# SparkFun_Qwiic_6DoF_BMI270.net
KiCad netlist of a schematic drawn in EAGLE
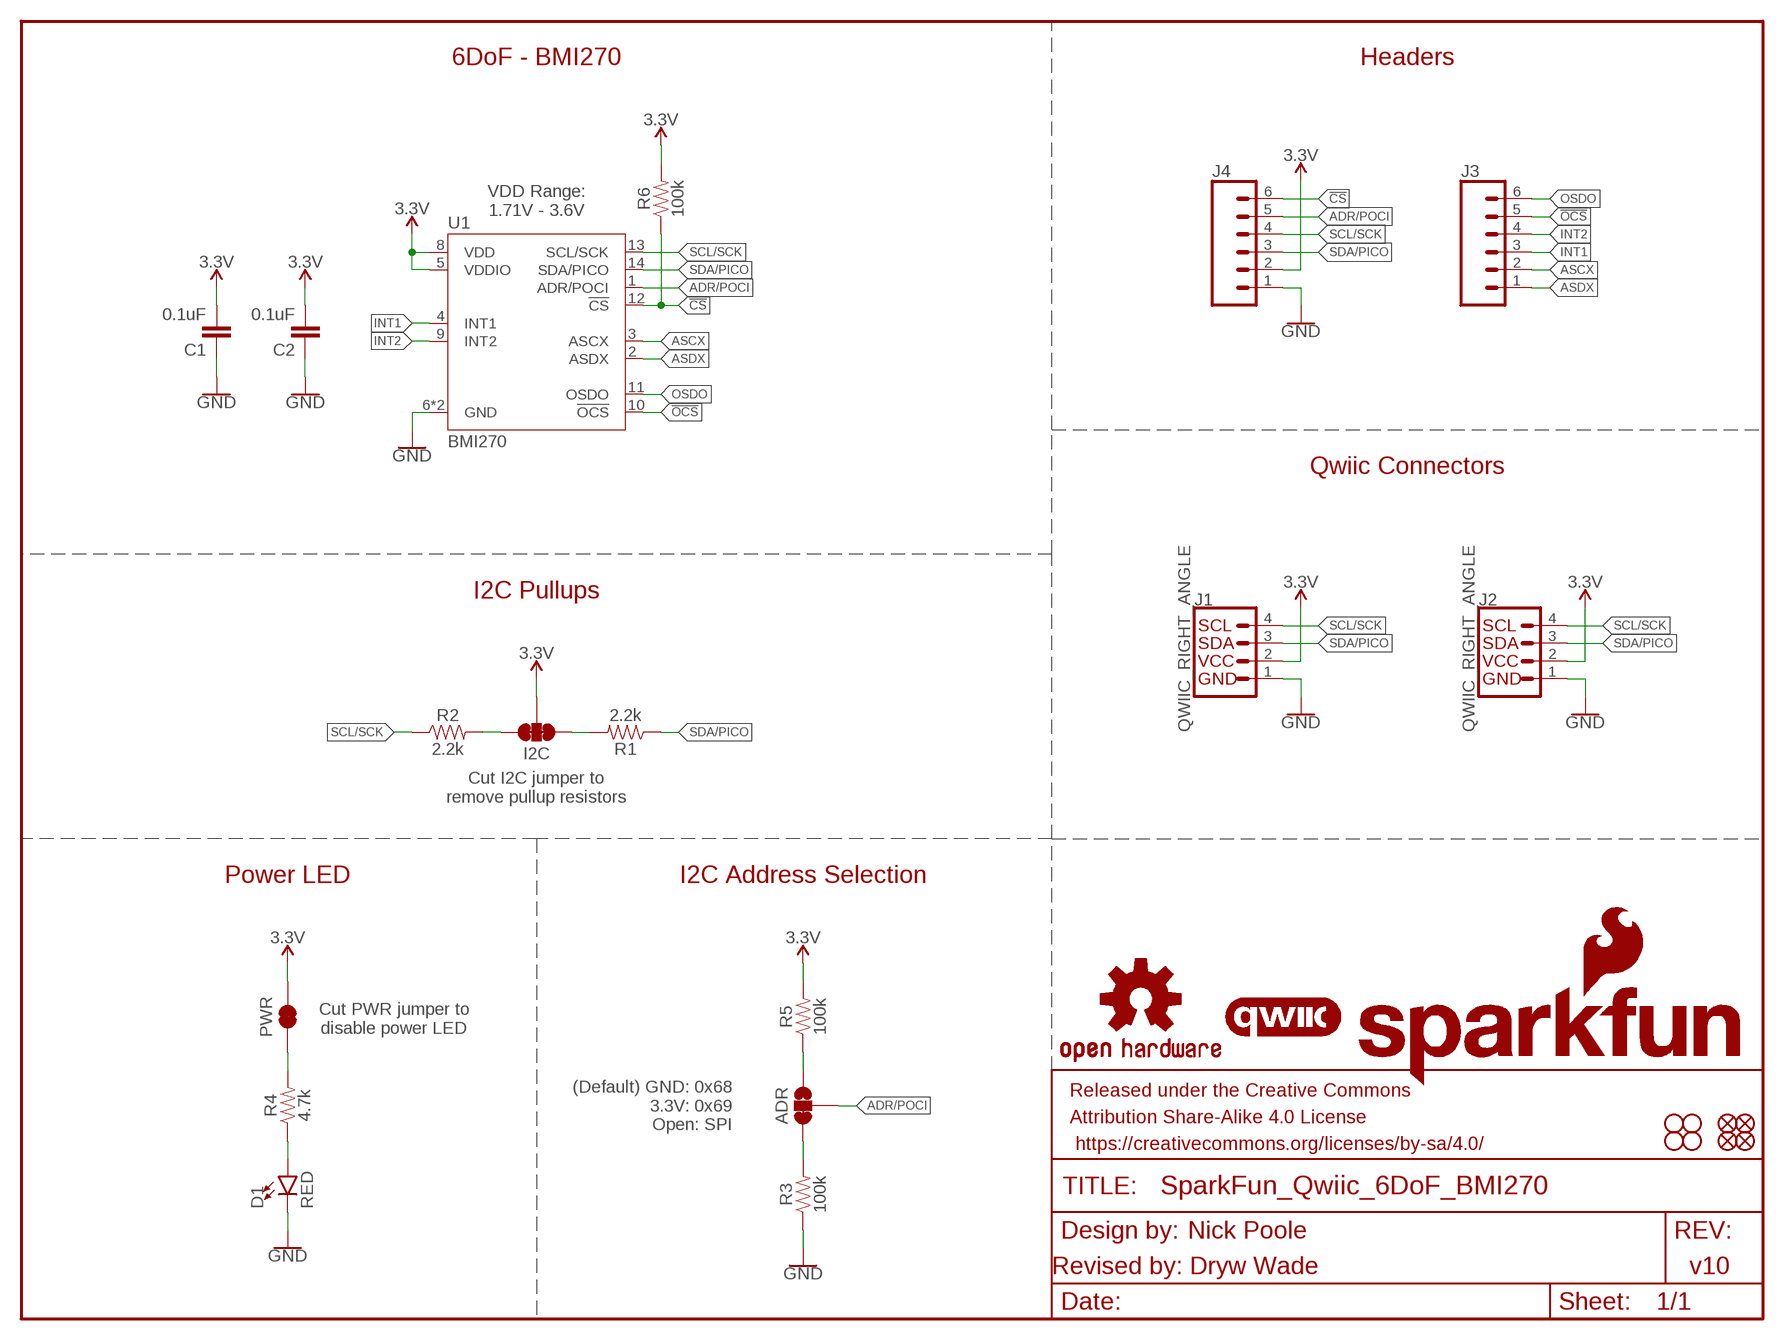
[diagram p0: schematic, sheet 1]

(export (version "E")
  (design (tool "Eeschema 10.0.6"))
  (components
    (comp (ref "ADR")
      (value "JUMPER-SMT_3_1-NC_TRACE_SILK")
      (footprint "eagle-import:SMT-JUMPER_3_1-NC_TRACE_SILK")
      (libsource (lib "eagle-import") (part "JUMPER-SMT_3_1-NC_TRACE_SILK"))
    )
    (comp (ref "C1")
      (value "0.1uF")
      (footprint "eagle-import:0603")
      (libsource (lib "eagle-import") (part "0.1UF-0603-25V-(+80/-20%)"))
    )
    (comp (ref "C2")
      (value "0.1uF")
      (footprint "eagle-import:0603")
      (libsource (lib "eagle-import") (part "0.1UF-0603-25V-(+80/-20%)"))
    )
    (comp (ref "D1")
      (value "RED")
      (footprint "eagle-import:LED-0603")
      (libsource (lib "eagle-import") (part "LED-RED_0603-KB"))
    )
    (comp (ref "FD1")
      (value "FIDUCIAL1X2")
      (footprint "eagle-import:FIDUCIAL-1X2")
      (libsource (lib "eagle-import") (part "FIDUCIAL1X2"))
    )
    (comp (ref "FD2")
      (value "FIDUCIAL1X2")
      (footprint "eagle-import:FIDUCIAL-1X2")
      (libsource (lib "eagle-import") (part "FIDUCIAL1X2"))
    )
    (comp (ref "FD3")
      (value "FIDUCIAL1X2")
      (footprint "eagle-import:FIDUCIAL-1X2")
      (libsource (lib "eagle-import") (part "FIDUCIAL1X2"))
    )
    (comp (ref "FD4")
      (value "FIDUCIAL1X2")
      (footprint "eagle-import:FIDUCIAL-1X2")
      (libsource (lib "eagle-import") (part "FIDUCIAL1X2"))
    )
    (comp (ref "FRAME1")
      (value "FRAME-LETTER")
      (footprint "eagle-import:CREATIVE_COMMONS")
      (libsource (lib "eagle-import") (part "FRAME-LETTER"))
    )
    (comp (ref "H1")
      (value "STAND-OFF")
      (footprint "eagle-import:STAND-OFF")
      (libsource (lib "eagle-import") (part "STAND-OFF"))
    )
    (comp (ref "H2")
      (value "STAND-OFF")
      (footprint "eagle-import:STAND-OFF")
      (libsource (lib "eagle-import") (part "STAND-OFF"))
    )
    (comp (ref "H3")
      (value "STAND-OFF")
      (footprint "eagle-import:STAND-OFF")
      (libsource (lib "eagle-import") (part "STAND-OFF"))
    )
    (comp (ref "H4")
      (value "STAND-OFF")
      (footprint "eagle-import:STAND-OFF")
      (libsource (lib "eagle-import") (part "STAND-OFF"))
    )
    (comp (ref "I2C")
      (value "JUMPER-SMT_3_2-NC_TRACE_SILK")
      (footprint "eagle-import:SMT-JUMPER_3_2-NC_TRACE_SILK")
      (libsource (lib "eagle-import") (part "JUMPER-SMT_3_2-NC_TRACE_SILK"))
    )
    (comp (ref "J1")
      (value "QWIIC_RIGHT_ANGLE")
      (footprint "eagle-import:JST04_1MM_RA")
      (libsource (lib "eagle-import") (part "QWIIC_CONNECTORJS-1MM"))
    )
    (comp (ref "J2")
      (value "QWIIC_RIGHT_ANGLE")
      (footprint "eagle-import:JST04_1MM_RA")
      (libsource (lib "eagle-import") (part "QWIIC_CONNECTORJS-1MM"))
    )
    (comp (ref "J3")
      (value "CONN_06NO_SILK_NO_POP")
      (footprint "eagle-import:1X06_NO_SILK")
      (libsource (lib "eagle-import") (part "CONN_06NO_SILK_NO_POP"))
    )
    (comp (ref "J4")
      (value "CONN_06NO_SILK_NO_POP")
      (footprint "eagle-import:1X06_NO_SILK")
      (libsource (lib "eagle-import") (part "CONN_06NO_SILK_NO_POP"))
    )
    (comp (ref "LOGO1")
      (value "SFE_LOGO_NAME_FLAME.1_INCH")
      (footprint "eagle-import:SFE_LOGO_NAME_FLAME_.1")
      (libsource (lib "eagle-import") (part "SFE_LOGO_NAME_FLAME.1_INCH"))
    )
    (comp (ref "LOGO2")
      (value "QWIIC_LOGO_5MM")
      (footprint "eagle-import:QWIIC_5MM")
      (libsource (lib "eagle-import") (part "QWIIC_LOGO_5MM"))
    )
    (comp (ref "LOGO3")
      (value "OSHW-LOGOS")
      (footprint "eagle-import:OSHW-LOGO-S")
      (libsource (lib "eagle-import") (part "OSHW-LOGOS"))
    )
    (comp (ref "PWR")
      (value "JUMPER-SMT_2_NC_TRACE_SILK")
      (footprint "eagle-import:SMT-JUMPER_2_NC_TRACE_SILK")
      (libsource (lib "eagle-import") (part "JUMPER-SMT_2_NC_TRACE_SILK"))
    )
    (comp (ref "R1")
      (value "2.2k")
      (footprint "eagle-import:0603")
      (libsource (lib "eagle-import") (part "2.2KOHM-0603-1/10W-1%"))
    )
    (comp (ref "R2")
      (value "2.2k")
      (footprint "eagle-import:0603")
      (libsource (lib "eagle-import") (part "2.2KOHM-0603-1/10W-1%"))
    )
    (comp (ref "R3")
      (value "100k")
      (footprint "eagle-import:0603")
      (libsource (lib "eagle-import") (part "100KOHM-0603-1/10W-1%"))
    )
    (comp (ref "R4")
      (value "4.7k")
      (footprint "eagle-import:0603")
      (libsource (lib "eagle-import") (part "4.7KOHM-0603-1/10W-1%"))
    )
    (comp (ref "R5")
      (value "100k")
      (footprint "eagle-import:0603")
      (libsource (lib "eagle-import") (part "100KOHM-0603-1/10W-1%"))
    )
    (comp (ref "R6")
      (value "100k")
      (footprint "eagle-import:0603")
      (libsource (lib "eagle-import") (part "100KOHM-0603-1/10W-1%"))
    )
    (comp (ref "U1")
      (value "BMI270")
      (footprint "eagle-import:BMI270")
      (libsource (lib "eagle-import") (part "BMI270"))
    )
  )
  (nets
    (net (code "1") (name "/~{CS}") (class "Default")
      (node (ref "J4") (pin "6") (pinfunction "6_6") (pintype "passive"))
      (node (ref "R6") (pin "1") (pinfunction "1_1") (pintype "passive"))
      (node (ref "U1") (pin "12") (pinfunction "~{CS}_12") (pintype "bidirectional"))
    )
    (net (code "2") (name "/~{OCS}") (class "Default")
      (node (ref "J3") (pin "5") (pinfunction "5_5") (pintype "passive"))
      (node (ref "U1") (pin "10") (pinfunction "~{OCS}_10") (pintype "bidirectional"))
    )
    (net (code "3") (name "3.3V") (class "Default")
      (node (ref "C1") (pin "2") (pinfunction "2_2") (pintype "passive"))
      (node (ref "C2") (pin "2") (pinfunction "2_2") (pintype "passive"))
      (node (ref "I2C") (pin "2") (pinfunction "2_2") (pintype "passive"))
      (node (ref "J1") (pin "2") (pinfunction "2_2") (pintype "power_in"))
      (node (ref "J2") (pin "2") (pinfunction "2_2") (pintype "power_in"))
      (node (ref "J4") (pin "2") (pinfunction "2_2") (pintype "passive"))
      (node (ref "PWR") (pin "2") (pinfunction "2_2") (pintype "passive"))
      (node (ref "R5") (pin "2") (pinfunction "2_2") (pintype "passive"))
      (node (ref "R6") (pin "2") (pinfunction "2_2") (pintype "passive"))
      (node (ref "U1") (pin "5") (pinfunction "VDDIO_5") (pintype "bidirectional"))
      (node (ref "U1") (pin "8") (pinfunction "VDD_8") (pintype "bidirectional"))
    )
    (net (code "4") (name "ADR{slash}POCI") (class "Default")
      (node (ref "ADR") (pin "2") (pinfunction "2_2") (pintype "passive"))
      (node (ref "J4") (pin "5") (pinfunction "5_5") (pintype "passive"))
      (node (ref "U1") (pin "1") (pinfunction "ADR/POCI_1") (pintype "bidirectional"))
    )
    (net (code "5") (name "ASCX") (class "Default")
      (node (ref "J3") (pin "2") (pinfunction "2_2") (pintype "passive"))
      (node (ref "U1") (pin "3") (pinfunction "ASCX_3") (pintype "bidirectional"))
    )
    (net (code "6") (name "ASDX") (class "Default")
      (node (ref "J3") (pin "1") (pinfunction "1_1") (pintype "passive"))
      (node (ref "U1") (pin "2") (pinfunction "ASDX_2") (pintype "bidirectional"))
    )
    (net (code "7") (name "GND") (class "Default")
      (node (ref "C1") (pin "1") (pinfunction "1_1") (pintype "passive"))
      (node (ref "C2") (pin "1") (pinfunction "1_1") (pintype "passive"))
      (node (ref "D1") (pin "C") (pinfunction "C_C") (pintype "passive"))
      (node (ref "J1") (pin "1") (pinfunction "1_1") (pintype "power_in"))
      (node (ref "J2") (pin "1") (pinfunction "1_1") (pintype "power_in"))
      (node (ref "J4") (pin "1") (pinfunction "1_1") (pintype "passive"))
      (node (ref "R3") (pin "1") (pinfunction "1_1") (pintype "passive"))
      (node (ref "U1") (pin "6") (pinfunction "GND_6") (pintype "bidirectional"))
      (node (ref "U1") (pin "7") (pinfunction "GND_7") (pintype "bidirectional"))
    )
    (net (code "8") (name "INT1") (class "Default")
      (node (ref "J3") (pin "3") (pinfunction "3_3") (pintype "passive"))
      (node (ref "U1") (pin "4") (pinfunction "INT1_4") (pintype "bidirectional"))
    )
    (net (code "9") (name "INT2") (class "Default")
      (node (ref "J3") (pin "4") (pinfunction "4_4") (pintype "passive"))
      (node (ref "U1") (pin "9") (pinfunction "INT2_9") (pintype "bidirectional"))
    )
    (net (code "10") (name "Net-(ADR-Pad1)") (class "Default")
      (node (ref "ADR") (pin "1") (pinfunction "1_1") (pintype "passive"))
      (node (ref "R5") (pin "1") (pinfunction "1_1") (pintype "passive"))
    )
    (net (code "11") (name "Net-(ADR-Pad3)") (class "Default")
      (node (ref "ADR") (pin "3") (pinfunction "3_3") (pintype "passive"))
      (node (ref "R3") (pin "2") (pinfunction "2_2") (pintype "passive"))
    )
    (net (code "12") (name "Net-(D1-PadA)") (class "Default")
      (node (ref "D1") (pin "A") (pinfunction "A_A") (pintype "passive"))
      (node (ref "R4") (pin "1") (pinfunction "1_1") (pintype "passive"))
    )
    (net (code "13") (name "Net-(I2C-Pad1)") (class "Default")
      (node (ref "I2C") (pin "1") (pinfunction "1_1") (pintype "passive"))
      (node (ref "R1") (pin "2") (pinfunction "2_2") (pintype "passive"))
    )
    (net (code "14") (name "Net-(I2C-Pad3)") (class "Default")
      (node (ref "I2C") (pin "3") (pinfunction "3_3") (pintype "passive"))
      (node (ref "R2") (pin "2") (pinfunction "2_2") (pintype "passive"))
    )
    (net (code "15") (name "Net-(PWR-Pad1)") (class "Default")
      (node (ref "PWR") (pin "1") (pinfunction "1_1") (pintype "passive"))
      (node (ref "R4") (pin "2") (pinfunction "2_2") (pintype "passive"))
    )
    (net (code "16") (name "OSDO") (class "Default")
      (node (ref "J3") (pin "6") (pinfunction "6_6") (pintype "passive"))
      (node (ref "U1") (pin "11") (pinfunction "OSDO_11") (pintype "bidirectional"))
    )
    (net (code "17") (name "SCL{slash}SCK") (class "Default")
      (node (ref "J1") (pin "4") (pinfunction "4_4") (pintype "passive"))
      (node (ref "J2") (pin "4") (pinfunction "4_4") (pintype "passive"))
      (node (ref "J4") (pin "4") (pinfunction "4_4") (pintype "passive"))
      (node (ref "R2") (pin "1") (pinfunction "1_1") (pintype "passive"))
      (node (ref "U1") (pin "13") (pinfunction "SCL/SCK_13") (pintype "bidirectional"))
    )
    (net (code "18") (name "SDA{slash}PICO") (class "Default")
      (node (ref "J1") (pin "3") (pinfunction "3_3") (pintype "passive"))
      (node (ref "J2") (pin "3") (pinfunction "3_3") (pintype "passive"))
      (node (ref "J4") (pin "3") (pinfunction "3_3") (pintype "passive"))
      (node (ref "R1") (pin "1") (pinfunction "1_1") (pintype "passive"))
      (node (ref "U1") (pin "14") (pinfunction "SDA/PICO_14") (pintype "bidirectional"))
    )
  )
)
